# USB_PD_CONTROLLER.net
KiCad netlist of a schematic drawn in Altium Designer
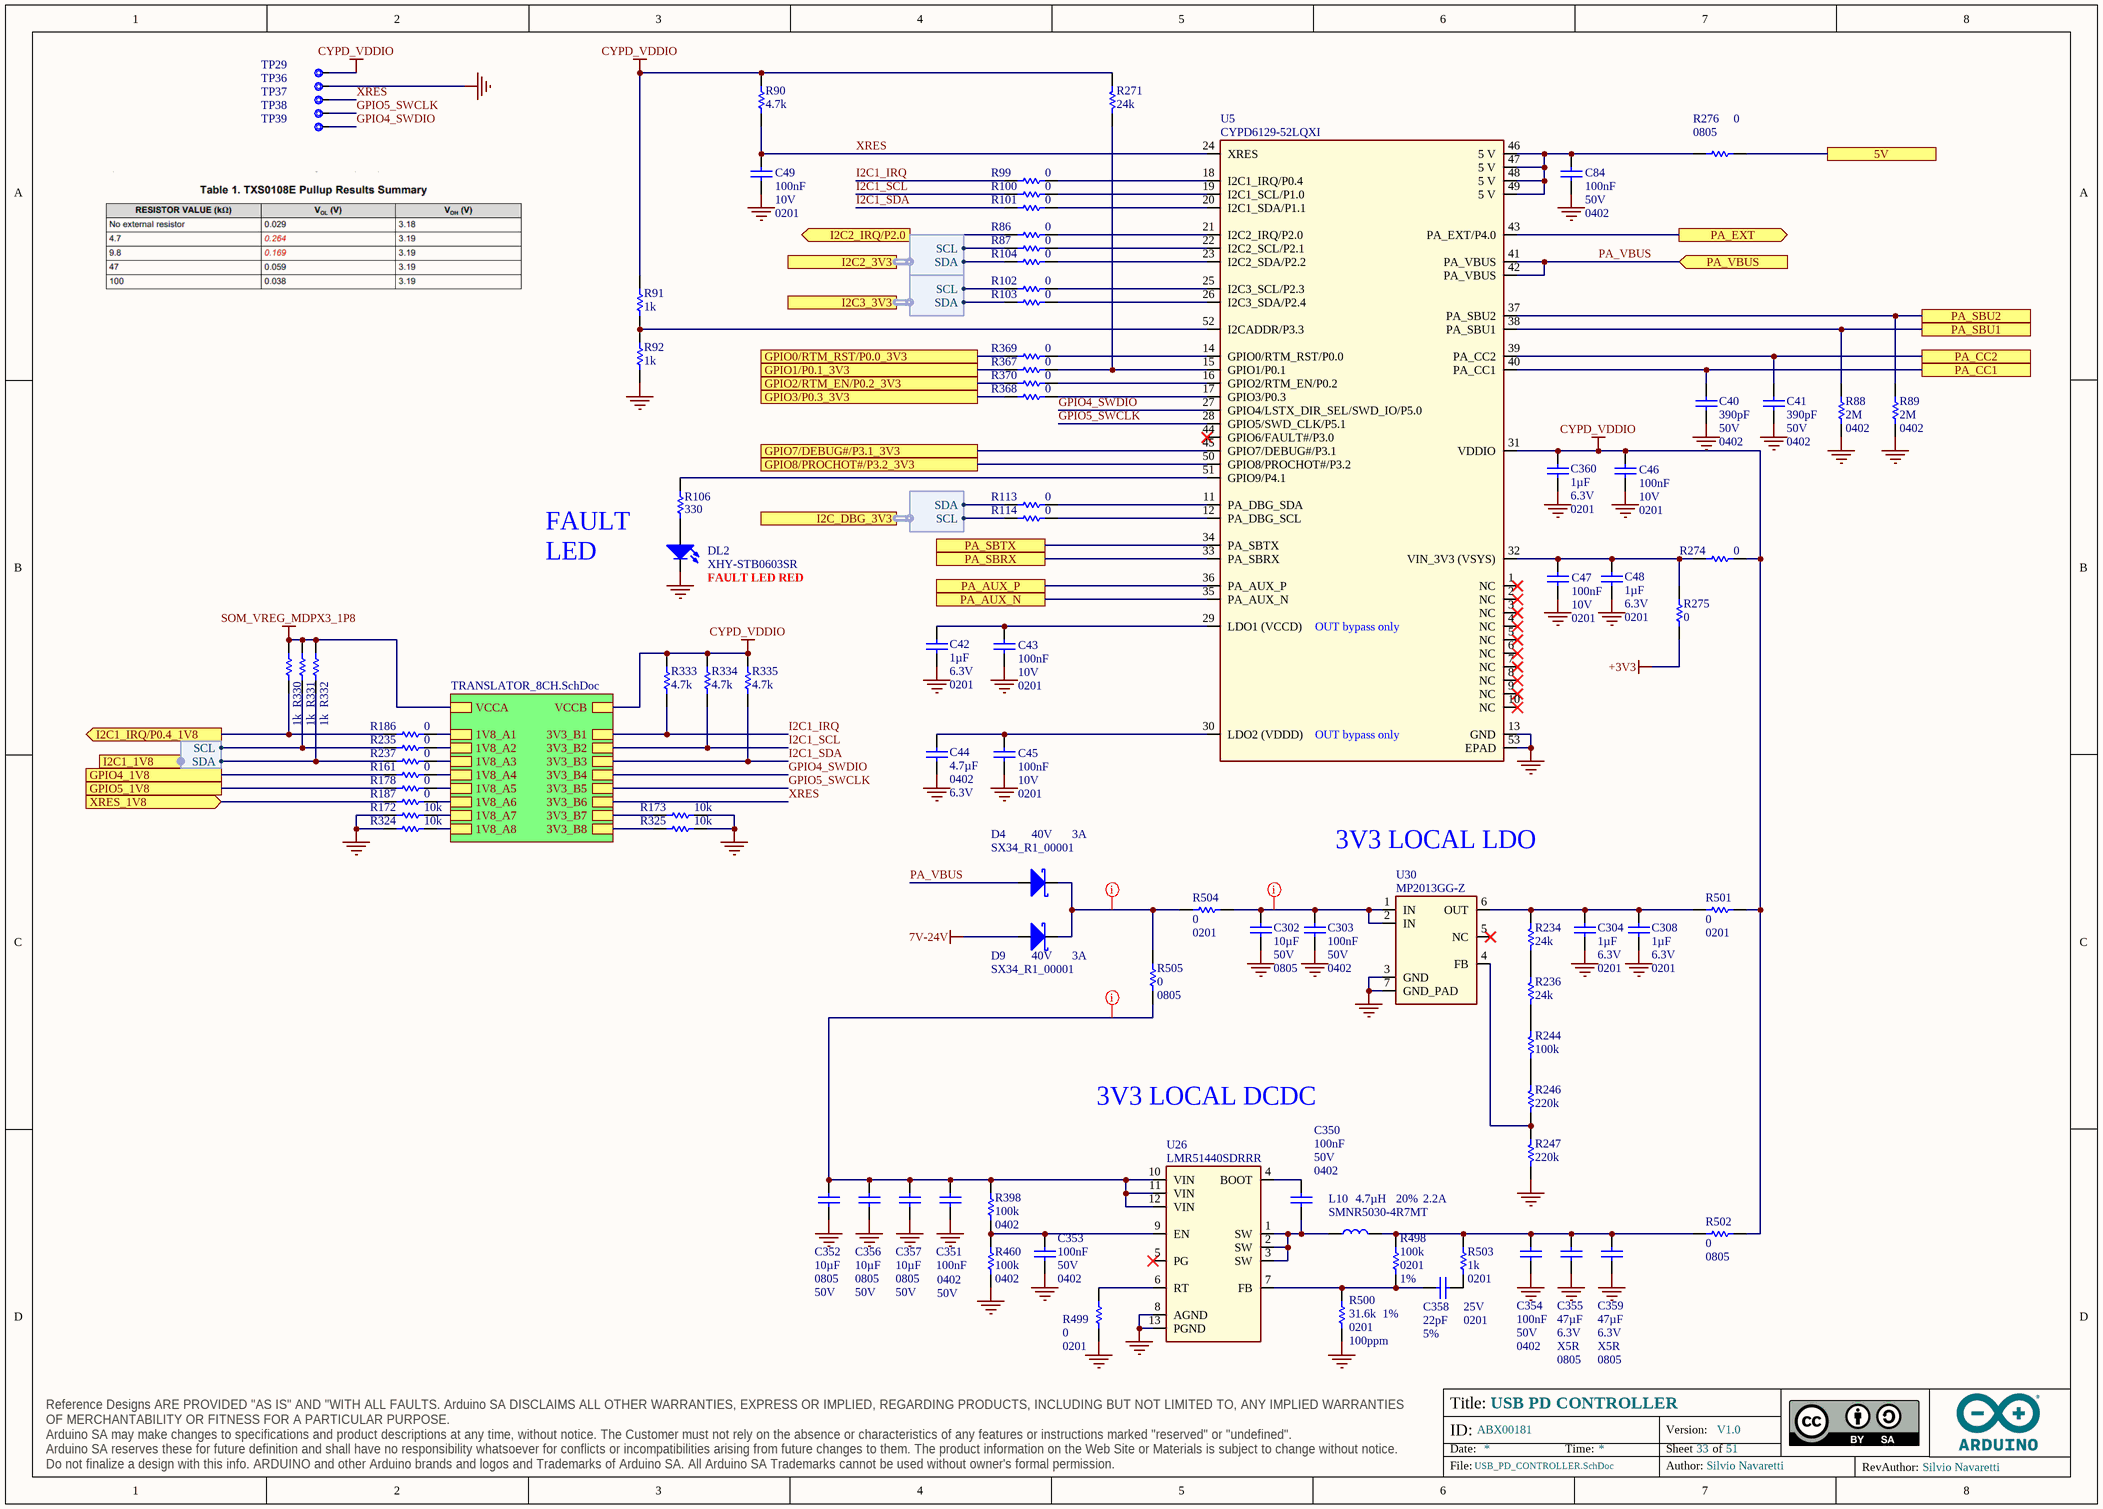
[diagram p0: USB_PD_CONTROLLER.SchDoc]

(export (version "E")
  (design (tool "Eeschema 10.0.6"))
  (components
    (comp (ref "C40")
      (value "390pF")
      (footprint "CAP-0402")
      (description "CAP CHIP 0402 390pF 10% 50V X7R")
      (fields
        (field (name "MANUFACTURER") "Murata")
        (field (name "PART NUMBER") "CL05B391KB5NNNC")
        (field (name "VOLTAGE") "50V")
        (field (name "CASE CODE (IMPERIAL)") "0402")
      )
      (libsource (lib "Clean") (part "CAP"))
    )
    (comp (ref "C41")
      (value "390pF")
      (footprint "CAP-0402")
      (description "CAP CHIP 0402 390pF 10% 50V X7R")
      (fields
        (field (name "MANUFACTURER") "Murata")
        (field (name "PART NUMBER") "CL05B391KB5NNNC")
        (field (name "VOLTAGE") "50V")
        (field (name "CASE CODE (IMPERIAL)") "0402")
      )
      (libsource (lib "Clean") (part "CAP"))
    )
    (comp (ref "C42")
      (value "1µF")
      (footprint "CAP-0201")
      (description "CAP CHIP 0201 1uF 20% 6.3V X5R")
      (fields
        (field (name "VOLTAGE") "6.3V")
        (field (name "TOLERANCE") "20%")
        (field (name "PART NUMBER") "GRM033R60J105MEA2D")
        (field (name "CASE CODE (IMPERIAL)") "0201")
      )
      (libsource (lib "Clean") (part "CAP"))
    )
    (comp (ref "C43")
      (value "100nF")
      (footprint "CAP-0201")
      (description "CAP CHIP 0201 100nF 10% 10V X5R")
      (fields
        (field (name "PART NUMBER") "CL03A104KP3NNNC")
        (field (name "MANUFACTURER") "Samsung Electro-Mechanics")
        (field (name "VOLTAGE") "10V")
        (field (name "CASE CODE (IMPERIAL)") "0201")
      )
      (libsource (lib "Clean") (part "CAP"))
    )
    (comp (ref "C44")
      (value "4.7µF")
      (footprint "CAP-0402")
      (description "CAP CHIP 0402 4.7uF 20% 6V3 X5R")
      (fields
        (field (name "MANUFACTURER") "Hottech")
        (field (name "PART NUMBER") "C1005A475M6R3NT")
        (field (name "CASE CODE (IMPERIAL)") "0402")
        (field (name "VOLTAGE") "6.3V")
      )
      (libsource (lib "Clean") (part "CAP"))
    )
    (comp (ref "C45")
      (value "100nF")
      (footprint "CAP-0201")
      (description "CAP CHIP 0201 100nF 10% 10V X5R")
      (fields
        (field (name "PART NUMBER") "CL03A104KP3NNNC")
        (field (name "MANUFACTURER") "Samsung Electro-Mechanics")
        (field (name "VOLTAGE") "10V")
        (field (name "CASE CODE (IMPERIAL)") "0201")
      )
      (libsource (lib "Clean") (part "CAP"))
    )
    (comp (ref "C46")
      (value "100nF")
      (footprint "CAP-0201")
      (description "CAP CHIP 0201 100nF 10% 10V X5R")
      (fields
        (field (name "PART NUMBER") "CL03A104KP3NNNC")
        (field (name "MANUFACTURER") "Samsung Electro-Mechanics")
        (field (name "VOLTAGE") "10V")
        (field (name "CASE CODE (IMPERIAL)") "0201")
      )
      (libsource (lib "Clean") (part "CAP"))
    )
    (comp (ref "C47")
      (value "100nF")
      (footprint "CAP-0201")
      (description "CAP CHIP 0201 100nF 10% 10V X5R")
      (fields
        (field (name "PART NUMBER") "CL03A104KP3NNNC")
        (field (name "MANUFACTURER") "Samsung Electro-Mechanics")
        (field (name "VOLTAGE") "10V")
        (field (name "CASE CODE (IMPERIAL)") "0201")
      )
      (libsource (lib "Clean") (part "CAP"))
    )
    (comp (ref "C48")
      (value "1µF")
      (footprint "CAP-0201")
      (description "CAP CHIP 0201 1uF 20% 6.3V X5R")
      (fields
        (field (name "VOLTAGE") "6.3V")
        (field (name "TOLERANCE") "20%")
        (field (name "PART NUMBER") "GRM033R60J105MEA2D")
        (field (name "CASE CODE (IMPERIAL)") "0201")
      )
      (libsource (lib "Clean") (part "CAP"))
    )
    (comp (ref "C49")
      (value "100nF")
      (footprint "CAP-0201")
      (description "CAP CHIP 0201 100nF 10% 10V X5R")
      (fields
        (field (name "PART NUMBER") "CL03A104KP3NNNC")
        (field (name "MANUFACTURER") "Samsung Electro-Mechanics")
        (field (name "VOLTAGE") "10V")
        (field (name "CASE CODE (IMPERIAL)") "0201")
      )
      (libsource (lib "Clean") (part "CAP"))
    )
    (comp (ref "C84")
      (value "100nF")
      (footprint "CAP-0402")
      (description "CAP CHIP 0402 100nF 10% 50V X5R")
      (fields
        (field (name "PART NUMBER") "GRM155R61H104KE19D")
        (field (name "MANUFACTURER") "Murata")
        (field (name "VOLTAGE") "50V")
        (field (name "CASE CODE (IMPERIAL)") "0402")
      )
      (libsource (lib "Clean") (part "CAP"))
    )
    (comp (ref "C302")
      (value "10µF")
      (footprint "CAP-0805")
      (description "CAP CHIP 0805 10uF 20% 50V X5R")
      (fields
        (field (name "VOLTAGE") "50V")
        (field (name "PART NUMBER") "GRM21BR61H106ME43L")
        (field (name "CASE CODE (IMPERIAL)") "0805")
        (field (name "MANUFACTURER") "Murata Electronics")
      )
      (libsource (lib "Clean") (part "CAP"))
    )
    (comp (ref "C303")
      (value "100nF")
      (footprint "CAP-0402")
      (description "CAP CHIP 0402 100nF 10% 50V X5R")
      (fields
        (field (name "MANUFACTURER") "Murata")
        (field (name "PART NUMBER") "GRM155R61H104KE19D")
        (field (name "VOLTAGE") "50V")
        (field (name "CASE CODE (IMPERIAL)") "0402")
      )
      (libsource (lib "Clean") (part "CAP"))
    )
    (comp (ref "C304")
      (value "1µF")
      (footprint "CAP-0201")
      (description "CAP CHIP 0201 1uF 20% 6.3V X5R")
      (fields
        (field (name "VOLTAGE") "6.3V")
        (field (name "TOLERANCE") "20%")
        (field (name "PART NUMBER") "GRM033R60J105MEA2D")
        (field (name "CASE CODE (IMPERIAL)") "0201")
      )
      (libsource (lib "Clean") (part "CAP"))
    )
    (comp (ref "C308")
      (value "1µF")
      (footprint "CAP-0201")
      (description "CAP CHIP 0201 1uF 20% 6.3V X5R")
      (fields
        (field (name "VOLTAGE") "6.3V")
        (field (name "TOLERANCE") "20%")
        (field (name "PART NUMBER") "GRM033R60J105MEA2D")
        (field (name "CASE CODE (IMPERIAL)") "0201")
      )
      (libsource (lib "Clean") (part "CAP"))
    )
    (comp (ref "C350")
      (value "100nF")
      (footprint "CAP-0402")
      (description "CAP CHIP 0402 100nF 10% 50V X5R")
      (fields
        (field (name "MANUFACTURER") "Murata")
        (field (name "PART NUMBER") "GRM155R61H104KE19D")
        (field (name "VOLTAGE") "50V")
        (field (name "CASE CODE (IMPERIAL)") "0402")
      )
      (libsource (lib "Clean") (part "CAP"))
    )
    (comp (ref "C351")
      (value "100nF")
      (footprint "CAP-0402")
      (description "CAP CHIP 0402 100nF 10% 50V X5R")
      (fields
        (field (name "MANUFACTURER") "Murata")
        (field (name "PART NUMBER") "GRM155R61H104KE19D")
        (field (name "VOLTAGE") "50V")
        (field (name "CASE CODE (IMPERIAL)") "0402")
      )
      (libsource (lib "Clean") (part "CAP"))
    )
    (comp (ref "C352")
      (value "10µF")
      (footprint "CAP-0805")
      (description "CAP CHIP 0805 10uF 20% 50V X5R")
      (fields
        (field (name "CASE CODE (IMPERIAL)") "0805")
        (field (name "TOLERANCE") "20%")
        (field (name "PART NUMBER") "GRM21BR61H106ME43L")
        (field (name "VOLTAGE") "50V")
      )
      (libsource (lib "Clean") (part "CAP"))
    )
    (comp (ref "C353")
      (value "100nF")
      (footprint "CAP-0402")
      (description "CAP CHIP 0402 100nF 10% 50V X5R")
      (fields
        (field (name "MANUFACTURER") "Murata")
        (field (name "PART NUMBER") "GRM155R61H104KE19D")
        (field (name "VOLTAGE") "50V")
        (field (name "CASE CODE (IMPERIAL)") "0402")
      )
      (libsource (lib "Clean") (part "CAP"))
    )
    (comp (ref "C354")
      (value "100nF")
      (footprint "CAP-0402")
      (description "CAP CHIP 0402 100nF 10% 50V X5R")
      (fields
        (field (name "MANUFACTURER") "Murata")
        (field (name "PART NUMBER") "GRM155R61H104KE19D")
        (field (name "VOLTAGE") "50V")
        (field (name "CASE CODE (IMPERIAL)") "0402")
      )
      (libsource (lib "Clean") (part "CAP"))
    )
    (comp (ref "C355")
      (value "47µF")
      (footprint "CAP-0805")
      (description "CAP CHIP 0805 47uF 20% 6.3V X5R")
      (fields
        (field (name "VOLTAGE") "6.3V")
        (field (name "DIELECTRIC") "X5R")
        (field (name "TOLERANCE") "20%")
        (field (name "CASE CODE (IMPERIAL)") "0805")
        (field (name "MANUFACTURER") "KEMET")
      )
      (libsource (lib "Clean") (part "CAP"))
    )
    (comp (ref "C356")
      (value "10µF")
      (footprint "CAP-0805")
      (description "CAP CHIP 0805 10uF 20% 50V X5R")
      (fields
        (field (name "CASE CODE (IMPERIAL)") "0805")
        (field (name "TOLERANCE") "20%")
        (field (name "PART NUMBER") "GRM21BR61H106ME43L")
        (field (name "VOLTAGE") "50V")
      )
      (libsource (lib "Clean") (part "CAP"))
    )
    (comp (ref "C357")
      (value "10µF")
      (footprint "CAP-0805")
      (description "CAP CHIP 0805 10uF 20% 50V X5R")
      (fields
        (field (name "CASE CODE (IMPERIAL)") "0805")
        (field (name "TOLERANCE") "20%")
        (field (name "PART NUMBER") "GRM21BR61H106ME43L")
        (field (name "VOLTAGE") "50V")
      )
      (libsource (lib "Clean") (part "CAP"))
    )
    (comp (ref "C358")
      (value "22pF")
      (footprint "CAP-0201")
      (description "CAP CHIP 0201 22pF 5% 25V C0G")
      (fields
        (field (name "TOLERANCE") "5%")
        (field (name "PART NUMBER") "CC0201JPNPO8BN220")
        (field (name "CASE CODE (IMPERIAL)") "0201")
        (field (name "MANUFACTURER") "Yageo")
        (field (name "VOLTAGE") "25V")
      )
      (libsource (lib "Clean") (part "CAP"))
    )
    (comp (ref "C359")
      (value "47µF")
      (footprint "CAP-0805")
      (description "CAP CHIP 0805 47uF 20% 6.3V X5R")
      (fields
        (field (name "VOLTAGE") "6.3V")
        (field (name "DIELECTRIC") "X5R")
        (field (name "TOLERANCE") "20%")
        (field (name "CASE CODE (IMPERIAL)") "0805")
        (field (name "MANUFACTURER") "KEMET")
      )
      (libsource (lib "Clean") (part "CAP"))
    )
    (comp (ref "C360")
      (value "1µF")
      (footprint "CAP-0201")
      (description "CAP CHIP 0201 1uF 20% 6.3V X5R")
      (fields
        (field (name "VOLTAGE") "6.3V")
        (field (name "TOLERANCE") "20%")
        (field (name "PART NUMBER") "GRM033R60J105MEA2D")
        (field (name "CASE CODE (IMPERIAL)") "0201")
      )
      (libsource (lib "Clean") (part "CAP"))
    )
    (comp (ref "D4")
      (value "SX34_R1_00001")
      (footprint "SMA DO214AC")
      (description "DIODE SCHOTTKY SMD 3A 40V SMA DO214AC")
      (fields
        (field (name "PART NUMBER") "SX34-AU_R1_000A1")
        (field (name "MANUFACTURER") "Panjit")
        (field (name "MAX REVERSE VOLTAGE (DC)") "40V")
        (field (name "FORWARD CURRENT") "3A")
      )
      (libsource (lib "Clean") (part "Diode Schottky"))
    )
    (comp (ref "D9")
      (value "SX34_R1_00001")
      (footprint "SMA DO214AC")
      (description "DIODE SCHOTTKY SMD 3A 40V SMA DO214AC")
      (fields
        (field (name "PART NUMBER") "SX34-AU_R1_000A1")
        (field (name "MANUFACTURER") "Panjit")
        (field (name "MAX REVERSE VOLTAGE (DC)") "40V")
        (field (name "FORWARD CURRENT") "3A")
      )
      (libsource (lib "Clean") (part "Diode Schottky"))
    )
    (comp (ref "DL2")
      (value "XHY-STB0603SR")
      (footprint "LEDC1608X80N-AK")
      (description "LED SMD 0603 RED 625nm, water clear, 42 to 88 mcd, 120 degrees, 1.6x0.8x0.6mm")
      (fields (field (name "MANUFACTURER") "Shenzen Corehy Technology"))
      (libsource (lib "Clean") (part "LED"))
    )
    (comp (ref "L10")
      (value "SMNR5030-4R7MT")
      (footprint "Inductor 5030")
      (description "IND SMD 4.7uH 20%, DCR max 65mR, I sat 3A, I RMS 2.2A, package 5x5mm height 3mm")
      (fields
        (field (name "MANUFACTURER") "Shun Xiang Nuo")
        (field (name "TOLERANCE") "20%")
        (field (name "IRMS") "2.2A")
        (field (name "INDUCTANCE") "4.7µH")
      )
      (libsource (lib "Clean") (part "Inductor"))
    )
    (comp (ref "R86")
      (value "0")
      (footprint "RES-0201")
      (description "RES CHIP 0201 0R")
      (fields (field (name "MANUFACTURER") "Vishay") (field (name "PART NUMBER") "CRCW02010000Z0ED"))
      (libsource (lib "Clean") (part "RES"))
    )
    (comp (ref "R87")
      (value "0")
      (footprint "RES-0201")
      (description "RES CHIP 0201 0R")
      (fields (field (name "MANUFACTURER") "Vishay") (field (name "PART NUMBER") "CRCW02010000Z0ED"))
      (libsource (lib "Clean") (part "RES"))
    )
    (comp (ref "R88")
      (value "2M")
      (footprint "RES-0402")
      (description "RES CHIP 0402 2M 1% 1/16W")
      (fields
        (field (name "PART NUMBER") "RC0402FR-072ML")
        (field (name "CASE CODE (IMPERIAL)") "0402")
        (field (name "MANUFACTURER") "YAGEO")
      )
      (libsource (lib "Clean") (part "RES"))
    )
    (comp (ref "R89")
      (value "2M")
      (footprint "RES-0402")
      (description "RES CHIP 0402 2M 1% 1/16W")
      (fields
        (field (name "PART NUMBER") "RC0402FR-072ML")
        (field (name "CASE CODE (IMPERIAL)") "0402")
        (field (name "MANUFACTURER") "YAGEO")
      )
      (libsource (lib "Clean") (part "RES"))
    )
    (comp (ref "R90")
      (value "4.7k")
      (footprint "RES-0201")
      (description "RES CHIP 0201 4k7 1% 1/20W")
      (fields (field (name "POWER") "50mW") (field (name "TOLERANCE") "1%"))
      (libsource (lib "Clean") (part "RES"))
    )
    (comp (ref "R91")
      (value "1k")
      (footprint "RES-0201")
      (description "RES CHIP 0201 1k 1% 1/20W")
      (fields (field (name "PART NUMBER") "RC0201FR-071KL") (field (name "TOLERANCE") "1%"))
      (libsource (lib "Clean") (part "RES"))
    )
    (comp (ref "R92")
      (value "1k")
      (footprint "RES-0201")
      (description "RES CHIP 0201 1k 1% 1/20W")
      (fields (field (name "PART NUMBER") "RC0201FR-071KL") (field (name "TOLERANCE") "1%"))
      (libsource (lib "Clean") (part "RES"))
    )
    (comp (ref "R99")
      (value "0")
      (footprint "RES-0201")
      (description "RES CHIP 0201 0R")
      (fields (field (name "MANUFACTURER") "Vishay") (field (name "PART NUMBER") "CRCW02010000Z0ED"))
      (libsource (lib "Clean") (part "RES"))
    )
    (comp (ref "R100")
      (value "0")
      (footprint "RES-0201")
      (description "RES CHIP 0201 0R")
      (fields (field (name "MANUFACTURER") "Vishay") (field (name "PART NUMBER") "CRCW02010000Z0ED"))
      (libsource (lib "Clean") (part "RES"))
    )
    (comp (ref "R101")
      (value "0")
      (footprint "RES-0201")
      (description "RES CHIP 0201 0R")
      (fields (field (name "MANUFACTURER") "Vishay") (field (name "PART NUMBER") "CRCW02010000Z0ED"))
      (libsource (lib "Clean") (part "RES"))
    )
    (comp (ref "R102")
      (value "0")
      (footprint "RES-0201")
      (description "RES CHIP 0201 0R")
      (fields (field (name "MANUFACTURER") "Vishay") (field (name "PART NUMBER") "CRCW02010000Z0ED"))
      (libsource (lib "Clean") (part "RES"))
    )
    (comp (ref "R103")
      (value "0")
      (footprint "RES-0201")
      (description "RES CHIP 0201 0R")
      (fields (field (name "MANUFACTURER") "Vishay") (field (name "PART NUMBER") "CRCW02010000Z0ED"))
      (libsource (lib "Clean") (part "RES"))
    )
    (comp (ref "R104")
      (value "0")
      (footprint "RES-0201")
      (description "RES CHIP 0201 0R")
      (fields (field (name "MANUFACTURER") "Vishay") (field (name "PART NUMBER") "CRCW02010000Z0ED"))
      (libsource (lib "Clean") (part "RES"))
    )
    (comp (ref "R106")
      (value "330")
      (footprint "RES-0201")
      (description "RES CHIP 0201 330R 1% 1/20W")
      (fields (field (name "MANUFACTURER") "Yageo") (field (name "POWER") "50mW"))
      (libsource (lib "Clean") (part "RES"))
    )
    (comp (ref "R113")
      (value "0")
      (footprint "RES-0201")
      (description "RES CHIP 0201 0R")
      (fields (field (name "MANUFACTURER") "Vishay") (field (name "PART NUMBER") "CRCW02010000Z0ED"))
      (libsource (lib "Clean") (part "RES"))
    )
    (comp (ref "R114")
      (value "0")
      (footprint "RES-0201")
      (description "RES CHIP 0201 0R")
      (fields (field (name "MANUFACTURER") "Vishay") (field (name "PART NUMBER") "CRCW02010000Z0ED"))
      (libsource (lib "Clean") (part "RES"))
    )
    (comp (ref "R161")
      (value "0")
      (footprint "RES-0201")
      (description "RES CHIP 0201 0R")
      (fields (field (name "MANUFACTURER") "Vishay") (field (name "PART NUMBER") "CRCW02010000Z0ED"))
      (libsource (lib "Clean") (part "RES"))
    )
    (comp (ref "R172")
      (value "10k")
      (footprint "RES-0201")
      (description "RES CHIP 0201 10k 1% 1/20W")
      (fields (field (name "POWER") "50mW") (field (name "TOLERANCE") "1%"))
      (libsource (lib "Clean") (part "RES"))
    )
    (comp (ref "R173")
      (value "10k")
      (footprint "RES-0201")
      (description "RES CHIP 0201 10k 1% 1/20W")
      (fields (field (name "POWER") "50mW") (field (name "TOLERANCE") "1%"))
      (libsource (lib "Clean") (part "RES"))
    )
    (comp (ref "R178")
      (value "0")
      (footprint "RES-0201")
      (description "RES CHIP 0201 0R")
      (fields (field (name "MANUFACTURER") "Vishay") (field (name "PART NUMBER") "CRCW02010000Z0ED"))
      (libsource (lib "Clean") (part "RES"))
    )
    (comp (ref "R186")
      (value "0")
      (footprint "RES-0201")
      (description "RES CHIP 0201 0R")
      (fields (field (name "MANUFACTURER") "Vishay") (field (name "PART NUMBER") "CRCW02010000Z0ED"))
      (libsource (lib "Clean") (part "RES"))
    )
    (comp (ref "R187")
      (value "0")
      (footprint "RES-0201")
      (description "RES CHIP 0201 0R")
      (fields (field (name "MANUFACTURER") "Vishay") (field (name "PART NUMBER") "CRCW02010000Z0ED"))
      (libsource (lib "Clean") (part "RES"))
    )
    (comp (ref "R234")
      (value "24k")
      (footprint "RES-0201")
      (description "RES CHIP 0201 24k 1% 1/20W")
      (fields (field (name "POWER") "50mW") (field (name "PART NUMBER") "RC0201FR-0724KL"))
      (libsource (lib "Clean") (part "RES"))
    )
    (comp (ref "R235")
      (value "0")
      (footprint "RES-0201")
      (description "RES CHIP 0201 0R")
      (fields (field (name "MANUFACTURER") "Vishay") (field (name "PART NUMBER") "CRCW02010000Z0ED"))
      (libsource (lib "Clean") (part "RES"))
    )
    (comp (ref "R236")
      (value "24k")
      (footprint "RES-0201")
      (description "RES CHIP 0201 24k 1% 1/20W")
      (fields (field (name "POWER") "50mW") (field (name "PART NUMBER") "RC0201FR-0724KL"))
      (libsource (lib "Clean") (part "RES"))
    )
    (comp (ref "R237")
      (value "0")
      (footprint "RES-0201")
      (description "RES CHIP 0201 0R")
      (fields (field (name "MANUFACTURER") "Vishay") (field (name "PART NUMBER") "CRCW02010000Z0ED"))
      (libsource (lib "Clean") (part "RES"))
    )
    (comp (ref "R244")
      (value "100k")
      (footprint "RES-0201")
      (description "RES CHIP 0201 100k 1% 1/20W")
      (fields (field (name "POWER") "50mW") (field (name "TOLERANCE") "1%"))
      (libsource (lib "Clean") (part "RES"))
    )
    (comp (ref "R246")
      (value "220k")
      (footprint "RES-0201")
      (description "RES CHIP 0201 220k 1% 1/20W")
      (fields (field (name "PART NUMBER") "AC0201FR-07220KL") (field (name "TOLERANCE") "1%"))
      (libsource (lib "Clean") (part "RES"))
    )
    (comp (ref "R247")
      (value "220k")
      (footprint "RES-0201")
      (description "RES CHIP 0201 220k 1% 1/20W")
      (fields (field (name "PART NUMBER") "AC0201FR-07220KL") (field (name "TOLERANCE") "1%"))
      (libsource (lib "Clean") (part "RES"))
    )
    (comp (ref "R271")
      (value "24k")
      (footprint "RES-0201")
      (description "RES CHIP 0201 24k 1% 1/20W")
      (fields (field (name "POWER") "50mW") (field (name "PART NUMBER") "RC0201FR-0724KL"))
      (libsource (lib "Clean") (part "RES"))
    )
    (comp (ref "R274")
      (value "0")
      (footprint "RES-0201")
      (description "RES CHIP 0201 0R")
      (fields (field (name "MANUFACTURER") "Vishay") (field (name "PART NUMBER") "CRCW02010000Z0ED"))
      (libsource (lib "Clean") (part "RES"))
    )
    (comp (ref "R275")
      (value "0")
      (footprint "RES-0201")
      (description "RES CHIP 0201 0R")
      (fields (field (name "MANUFACTURER") "Vishay") (field (name "PART NUMBER") "CRCW02010000Z0ED"))
      (libsource (lib "Clean") (part "RES"))
    )
    (comp (ref "R276")
      (value "0")
      (footprint "RES-0805")
      (description "RES CHIP 0805 0R")
      (fields
        (field (name "MANUFACTURER") "Vishay")
        (field (name "CASE CODE (IMPERIAL)") "0805")
        (field (name "PART NUMBER") "CRCW08050000Z0EB")
      )
      (libsource (lib "Clean") (part "RES"))
    )
    (comp (ref "R324")
      (value "10k")
      (footprint "RES-0201")
      (description "RES CHIP 0201 10k 1% 1/20W")
      (fields (field (name "POWER") "50mW") (field (name "TOLERANCE") "1%"))
      (libsource (lib "Clean") (part "RES"))
    )
    (comp (ref "R325")
      (value "10k")
      (footprint "RES-0201")
      (description "RES CHIP 0201 10k 1% 1/20W")
      (fields (field (name "POWER") "50mW") (field (name "TOLERANCE") "1%"))
      (libsource (lib "Clean") (part "RES"))
    )
    (comp (ref "R330")
      (value "1k")
      (footprint "RES-0201")
      (description "RES CHIP 0201 1k 1% 1/20W")
      (fields (field (name "POWER") "50mW") (field (name "TOLERANCE") "1%"))
      (libsource (lib "Clean") (part "RES"))
    )
    (comp (ref "R331")
      (value "1k")
      (footprint "RES-0201")
      (description "RES CHIP 0201 1k 1% 1/20W")
      (fields (field (name "POWER") "50mW") (field (name "TOLERANCE") "1%"))
      (libsource (lib "Clean") (part "RES"))
    )
    (comp (ref "R332")
      (value "1k")
      (footprint "RES-0201")
      (description "RES CHIP 0201 1k 1% 1/20W")
      (fields (field (name "POWER") "50mW") (field (name "TOLERANCE") "1%"))
      (libsource (lib "Clean") (part "RES"))
    )
    (comp (ref "R333")
      (value "4.7k")
      (footprint "RES-0201")
      (description "RES CHIP 0201 4k7 1% 1/20W")
      (fields (field (name "POWER") "50mW") (field (name "TOLERANCE") "1%"))
      (libsource (lib "Clean") (part "RES"))
    )
    (comp (ref "R334")
      (value "4.7k")
      (footprint "RES-0201")
      (description "RES CHIP 0201 4k7 1% 1/20W")
      (fields (field (name "POWER") "50mW") (field (name "TOLERANCE") "1%"))
      (libsource (lib "Clean") (part "RES"))
    )
    (comp (ref "R335")
      (value "4.7k")
      (footprint "RES-0201")
      (description "RES CHIP 0201 4k7 1% 1/20W")
      (fields (field (name "POWER") "50mW") (field (name "TOLERANCE") "1%"))
      (libsource (lib "Clean") (part "RES"))
    )
    (comp (ref "R367")
      (value "0")
      (footprint "RES-0201")
      (description "RES CHIP 0201 0R")
      (fields (field (name "MANUFACTURER") "Vishay") (field (name "PART NUMBER") "CRCW02010000Z0ED"))
      (libsource (lib "Clean") (part "RES"))
    )
    (comp (ref "R368")
      (value "0")
      (footprint "RES-0201")
      (description "RES CHIP 0201 0R")
      (fields (field (name "MANUFACTURER") "Vishay") (field (name "PART NUMBER") "CRCW02010000Z0ED"))
      (libsource (lib "Clean") (part "RES"))
    )
    (comp (ref "R369")
      (value "0")
      (footprint "RES-0201")
      (description "RES CHIP 0201 0R")
      (fields (field (name "MANUFACTURER") "Vishay") (field (name "PART NUMBER") "CRCW02010000Z0ED"))
      (libsource (lib "Clean") (part "RES"))
    )
    (comp (ref "R370")
      (value "0")
      (footprint "RES-0201")
      (description "RES CHIP 0201 0R")
      (fields (field (name "MANUFACTURER") "Vishay") (field (name "PART NUMBER") "CRCW02010000Z0ED"))
      (libsource (lib "Clean") (part "RES"))
    )
    (comp (ref "R398")
      (value "100k")
      (footprint "RES-0402")
      (description "RES CHIP 0402 100k 1% 1/16W")
      (fields
        (field (name "MANUFACTURER") "Vishay")
        (field (name "PART NUMBER") "CRCW0402100KFKEDC")
        (field (name "CASE CODE (IMPERIAL)") "0402")
      )
      (libsource (lib "Clean") (part "RES"))
    )
    (comp (ref "R460")
      (value "100k")
      (footprint "RES-0402")
      (description "RES CHIP 0402 100k 1% 1/16W")
      (fields
        (field (name "MANUFACTURER") "Vishay")
        (field (name "PART NUMBER") "CRCW0402100KFKEDC")
        (field (name "CASE CODE (IMPERIAL)") "0402")
      )
      (libsource (lib "Clean") (part "RES"))
    )
    (comp (ref "R498")
      (value "100k")
      (footprint "RES-0201")
      (description "RES CHIP 0201 100k 1% 1/20W")
      (fields
        (field (name "MANUFACTURER") "Yageo")
        (field (name "PART NUMBER") "RC0201FR-07100KL")
        (field (name "TOLERANCE") "1%")
        (field (name "CASE CODE (IMPERIAL)") "0201")
      )
      (libsource (lib "Clean") (part "RES"))
    )
    (comp (ref "R499")
      (value "0")
      (footprint "RES-0201")
      (description "RES CHIP 0201 0R")
      (fields
        (field (name "MANUFACTURER") "Vishay")
        (field (name "CASE CODE (IMPERIAL)") "0201")
        (field (name "PART NUMBER") "CRCW02010000Z0ED")
      )
      (libsource (lib "Clean") (part "RES"))
    )
    (comp (ref "R500")
      (value "31.6k")
      (footprint "RES-0201")
      (description "RES CHIP 0201 31k6 1% 1/20W 100ppm")
      (fields
        (field (name "POWER") "50mW")
        (field (name "PART NUMBER") "CRCW020131K6FKED")
        (field (name "CASE CODE (IMPERIAL)") "0201")
        (field (name "TOLERANCE") "1%")
        (field (name "TEMPERATURE COEFFICIENT") "100ppm")
      )
      (libsource (lib "Clean") (part "RES"))
    )
    (comp (ref "R501")
      (value "0")
      (footprint "RES-0201")
      (description "RES CHIP 0201 0R")
      (fields
        (field (name "MANUFACTURER") "Vishay")
        (field (name "CASE CODE (IMPERIAL)") "0201")
        (field (name "PART NUMBER") "CRCW02010000Z0ED")
      )
      (libsource (lib "Clean") (part "RES"))
    )
    (comp (ref "R502")
      (value "0")
      (footprint "RES-0805")
      (description "RES CHIP 0805 0R")
      (fields
        (field (name "MANUFACTURER") "Vishay")
        (field (name "CASE CODE (IMPERIAL)") "0805")
        (field (name "PART NUMBER") "CRCW08050000Z0EB")
      )
      (libsource (lib "Clean") (part "RES"))
    )
    (comp (ref "R503")
      (value "1k")
      (footprint "RES-0201")
      (description "RES CHIP 0201 1k 1% 1/20W")
      (fields
        (field (name "PART NUMBER") "RC0201FR-071KL")
        (field (name "TOLERANCE") "1%")
        (field (name "CASE CODE (IMPERIAL)") "0201")
      )
      (libsource (lib "Clean") (part "RES"))
    )
    (comp (ref "R504")
      (value "0")
      (footprint "RES-0201")
      (description "RES CHIP 0201 0R")
      (fields
        (field (name "MANUFACTURER") "Vishay")
        (field (name "CASE CODE (IMPERIAL)") "0201")
        (field (name "PART NUMBER") "CRCW02010000Z0ED")
      )
      (libsource (lib "Clean") (part "RES"))
    )
    (comp (ref "R505")
      (value "0")
      (footprint "RES-0805")
      (description "RES CHIP 0805 0R")
      (fields
        (field (name "MANUFACTURER") "Vishay")
        (field (name "CASE CODE (IMPERIAL)") "0805")
        (field (name "PART NUMBER") "CRCW08050000Z0EB")
      )
      (libsource (lib "Clean") (part "RES"))
    )
    (comp (ref "TP29")
      (value "Test point 1.00mm")
      (footprint "TP-1.00MM")
      (fields (field (name "PART NUMBER") "This is not a component"))
      (libsource (lib "Clean") (part "TESTPOINT"))
    )
    (comp (ref "TP36")
      (value "Test point 1.00mm")
      (footprint "TP-1.00MM")
      (fields (field (name "PART NUMBER") "This is not a component"))
      (libsource (lib "Clean") (part "TESTPOINT"))
    )
    (comp (ref "TP37")
      (value "Test point 1.00mm")
      (footprint "TP-1.00MM")
      (fields (field (name "PART NUMBER") "This is not a component"))
      (libsource (lib "Clean") (part "TESTPOINT"))
    )
    (comp (ref "TP38")
      (value "Test point 1.00mm")
      (footprint "TP-1.00MM")
      (fields (field (name "PART NUMBER") "This is not a component"))
      (libsource (lib "Clean") (part "TESTPOINT"))
    )
    (comp (ref "TP39")
      (value "Test point 1.00mm")
      (footprint "TP-1.00MM")
      (fields (field (name "PART NUMBER") "This is not a component"))
      (libsource (lib "Clean") (part "TESTPOINT"))
    )
    (comp (ref "U5")
      (value "CYPD6129-52LQXI")
      (footprint "QFN52 pitch 0.4mm, 5x8mm")
      (description "IC Controller power delivery USB-C, QFN52 5x8mm")
      (fields (field (name "MANUFACTURER") "Infineon"))
      (libsource (lib "Clean") (part "CYPD6129-52LQXI-Symbol-1"))
    )
    (comp (ref "U26")
      (value "LMR51440SDRRR")
      (footprint "WSON8 TI DDR 3x3mm 12 pins pitch 0.5mm")
      (description "IC BUCK Vin 4-36V, Iout 4A, max duty 97%, fsw 1.1MHz, WSON8 3x3mm")
      (fields (field (name "MANUFACTURER") "Texas Instruments"))
      (libsource (lib "Clean") (part "LMR51440SDRRR-Symbol-1"))
    )
    (comp (ref "U30")
      (value "MP2013GG-Z")
      (footprint "MPS QNF6 2x2mm 6pin pitch 0.65mm thermal pad")
      (description "IC LDO, Vin 2.5V-40V, Vout ADJ, Iout 0.15A, Iq typ 15uA, QFN6 2x2mm")
      (fields (field (name "MANUFACTURER") "MPS"))
      (libsource (lib "Clean") (part "MP2013GG-Z"))
    )
  )
  (nets
    (net (code "3") (name "+3V3") (class "Default")
      (node (ref "R275") (pin "1") (pinfunction "1_1") (pintype "passive"))
    )
    (net (code "4") (name "/1V8_A1") (class "Default")
      (node (ref "R186") (pin "2") (pinfunction "2_2") (pintype "passive"))
    )
    (net (code "5") (name "/1V8_A2") (class "Default")
      (node (ref "R235") (pin "2") (pinfunction "2_2") (pintype "passive"))
    )
    (net (code "6") (name "/1V8_A3") (class "Default")
      (node (ref "R237") (pin "2") (pinfunction "2_2") (pintype "passive"))
    )
    (net (code "7") (name "/1V8_A4") (class "Default")
      (node (ref "R161") (pin "2") (pinfunction "2_2") (pintype "passive"))
    )
    (net (code "8") (name "/1V8_A5") (class "Default")
      (node (ref "R178") (pin "2") (pinfunction "2_2") (pintype "passive"))
    )
    (net (code "9") (name "/1V8_A6") (class "Default")
      (node (ref "R187") (pin "2") (pinfunction "2_2") (pintype "passive"))
    )
    (net (code "10") (name "/1V8_A7") (class "Default")
      (node (ref "R172") (pin "2") (pinfunction "2_2") (pintype "passive"))
    )
    (net (code "11") (name "/1V8_A8") (class "Default")
      (node (ref "R324") (pin "2") (pinfunction "2_2") (pintype "passive"))
    )
    (net (code "12") (name "/3V3_B7") (class "Default")
      (node (ref "R173") (pin "1") (pinfunction "1_1") (pintype "passive"))
    )
    (net (code "13") (name "/3V3_B8") (class "Default")
      (node (ref "R325") (pin "1") (pinfunction "1_1") (pintype "passive"))
    )
    (net (code "14") (name "/5V") (class "Default")
      (node (ref "R276") (pin "2") (pinfunction "2_2") (pintype "passive"))
    )
    (net (code "15") (name "/GPIO0{slash}RTM_RST{slash}P0.0_3V3") (class "Default")
      (node (ref "R369") (pin "1") (pinfunction "1_1") (pintype "passive"))
    )
    (net (code "16") (name "/GPIO1{slash}P0.1_3V3") (class "Default")
      (node (ref "R367") (pin "1") (pinfunction "1_1") (pintype "passive"))
    )
    (net (code "17") (name "/GPIO2{slash}RTM_EN{slash}P0.2_3V3") (class "Default")
      (node (ref "R370") (pin "1") (pinfunction "1_1") (pintype "passive"))
    )
    (net (code "18") (name "/GPIO3{slash}P0.3_3V3") (class "Default")
      (node (ref "R368") (pin "1") (pinfunction "1_1") (pintype "passive"))
    )
    (net (code "19") (name "/GPIO4_1V8") (class "Default")
      (node (ref "R161") (pin "1") (pinfunction "1_1") (pintype "passive"))
    )
    (net (code "20") (name "/GPIO4_SWDIO") (class "Default")
      (node (ref "TP39") (pin "X") (pinfunction "X_X") (pintype "passive"))
      (node (ref "U5") (pin "27") (pinfunction "GPIO4/LSTX_DIR_SEL/SWD_IO/P5.0_27") (pintype "passive"))
    )
    (net (code "21") (name "/GPIO5_1V8") (class "Default")
      (node (ref "R178") (pin "1") (pinfunction "1_1") (pintype "passive"))
    )
    (net (code "22") (name "/GPIO5_SWCLK") (class "Default")
      (node (ref "TP38") (pin "X") (pinfunction "X_X") (pintype "passive"))
      (node (ref "U5") (pin "28") (pinfunction "GPIO5/SWD_CLK/P5.1_28") (pintype "passive"))
    )
    (net (code "23") (name "/GPIO7{slash}DEBUG#{slash}P3.1_3V3") (class "Default")
      (node (ref "U5") (pin "45") (pinfunction "GPIO7/DEBUG#/P3.1_45") (pintype "passive"))
    )
    (net (code "24") (name "/GPIO8{slash}PROCHOT#{slash}P3.2_3V3") (class "Default")
      (node (ref "U5") (pin "50") (pinfunction "GPIO8/PROCHOT#/P3.2_50") (pintype "passive"))
    )
    (net (code "25") (name "/I2C1_IRQ") (class "Default")
      (node (ref "R333") (pin "2") (pinfunction "2_2") (pintype "passive"))
      (node (ref "R99") (pin "1") (pinfunction "1_1") (pintype "passive"))
    )
    (net (code "26") (name "/I2C1_IRQ{slash}P0.4_1V8") (class "Default")
      (node (ref "R186") (pin "1") (pinfunction "1_1") (pintype "passive"))
      (node (ref "R330") (pin "2") (pinfunction "2_2") (pintype "passive"))
    )
    (net (code "27") (name "/I2C1_SCL") (class "Default")
      (node (ref "R100") (pin "1") (pinfunction "1_1") (pintype "passive"))
      (node (ref "R334") (pin "2") (pinfunction "2_2") (pintype "passive"))
    )
    (net (code "28") (name "/I2C1_SDA") (class "Default")
      (node (ref "R101") (pin "1") (pinfunction "1_1") (pintype "passive"))
      (node (ref "R335") (pin "2") (pinfunction "2_2") (pintype "passive"))
    )
    (net (code "30") (name "/I2C2_IRQ{slash}P2.0") (class "Default")
      (node (ref "R86") (pin "1") (pinfunction "1_1") (pintype "passive"))
    )
    (net (code "31") (name "/PA_AUX_N") (class "Default")
      (node (ref "U5") (pin "35") (pinfunction "PA_AUX_N_35") (pintype "passive"))
    )
    (net (code "32") (name "/PA_AUX_P") (class "Default")
      (node (ref "U5") (pin "36") (pinfunction "PA_AUX_P_36") (pintype "passive"))
    )
    (net (code "33") (name "/PA_CC1") (class "Default")
      (node (ref "C40") (pin "2") (pinfunction "2_2") (pintype "passive"))
      (node (ref "U5") (pin "40") (pinfunction "PA_CC1_40") (pintype "passive"))
    )
    (net (code "34") (name "/PA_CC2") (class "Default")
      (node (ref "C41") (pin "2") (pinfunction "2_2") (pintype "passive"))
      (node (ref "U5") (pin "39") (pinfunction "PA_CC2_39") (pintype "passive"))
    )
    (net (code "35") (name "/PA_EXT") (class "Default")
      (node (ref "U5") (pin "43") (pinfunction "PA_EXT/P4.0_43") (pintype "passive"))
    )
    (net (code "36") (name "/PA_SBRX") (class "Default")
      (node (ref "U5") (pin "33") (pinfunction "PA_SBRX_33") (pintype "passive"))
    )
    (net (code "37") (name "/PA_SBTX") (class "Default")
      (node (ref "U5") (pin "34") (pinfunction "PA_SBTX_34") (pintype "passive"))
    )
    (net (code "38") (name "/PA_SBU1") (class "Default")
      (node (ref "R88") (pin "2") (pinfunction "2_2") (pintype "passive"))
      (node (ref "U5") (pin "38") (pinfunction "PA_SBU1_38") (pintype "passive"))
    )
    (net (code "39") (name "/PA_SBU2") (class "Default")
      (node (ref "R89") (pin "2") (pinfunction "2_2") (pintype "passive"))
      (node (ref "U5") (pin "37") (pinfunction "PA_SBU2_37") (pintype "passive"))
    )
    (net (code "40") (name "/PA_VBUS") (class "Default")
      (node (ref "D4") (pin "A") (pinfunction "A_A") (pintype "passive"))
      (node (ref "U5") (pin "41") (pinfunction "PA_VBUS_41") (pintype "passive"))
      (node (ref "U5") (pin "42") (pinfunction "PA_VBUS_42") (pintype "passive"))
    )
    (net (code "41") (name "/XRES") (class "Default")
      (node (ref "C49") (pin "2") (pinfunction "2_2") (pintype "passive"))
      (node (ref "R90") (pin "2") (pinfunction "2_2") (pintype "passive"))
      (node (ref "TP37") (pin "X") (pinfunction "X_X") (pintype "passive"))
      (node (ref "U5") (pin "24") (pinfunction "XRES_24") (pintype "passive"))
    )
    (net (code "42") (name "/XRES_1V8") (class "Default")
      (node (ref "R187") (pin "1") (pinfunction "1_1") (pintype "passive"))
    )
    (net (code "44") (name "7V-24V") (class "Default")
      (node (ref "D9") (pin "A") (pinfunction "A_A") (pintype "passive"))
    )
    (net (code "45") (name "CYPD_VDDIO") (class "Default")
      (node (ref "C360") (pin "2") (pinfunction "2_2") (pintype "passive"))
      (node (ref "C46") (pin "2") (pinfunction "2_2") (pintype "passive"))
      (node (ref "R271") (pin "2") (pinfunction "2_2") (pintype "passive"))
      (node (ref "R274") (pin "2") (pinfunction "2_2") (pintype "passive"))
      (node (ref "R333") (pin "1") (pinfunction "1_1") (pintype "passive"))
      (node (ref "R334") (pin "1") (pinfunction "1_1") (pintype "passive"))
      (node (ref "R335") (pin "1") (pinfunction "1_1") (pintype "passive"))
      (node (ref "R501") (pin "1") (pinfunction "1_1") (pintype "passive"))
      (node (ref "R502") (pin "2") (pinfunction "2_2") (pintype "passive"))
      (node (ref "R90") (pin "1") (pinfunction "1_1") (pintype "passive"))
      (node (ref "R91") (pin "1") (pinfunction "1_1") (pintype "passive"))
      (node (ref "TP29") (pin "X") (pinfunction "X_X") (pintype "passive"))
      (node (ref "U5") (pin "31") (pinfunction "VDDIO_31") (pintype "passive"))
    )
    (net (code "46") (name "GND") (class "Default")
      (node (ref "C302") (pin "1") (pinfunction "1_1") (pintype "passive"))
      (node (ref "C303") (pin "2") (pinfunction "2_2") (pintype "passive"))
      (node (ref "C304") (pin "1") (pinfunction "1_1") (pintype "passive"))
      (node (ref "C308") (pin "1") (pinfunction "1_1") (pintype "passive"))
      (node (ref "C351") (pin "2") (pinfunction "2_2") (pintype "passive"))
      (node (ref "C352") (pin "2") (pinfunction "2_2") (pintype "passive"))
      (node (ref "C353") (pin "2") (pinfunction "2_2") (pintype "passive"))
      (node (ref "C354") (pin "2") (pinfunction "2_2") (pintype "passive"))
      (node (ref "C355") (pin "1") (pinfunction "1_1") (pintype "passive"))
      (node (ref "C356") (pin "2") (pinfunction "2_2") (pintype "passive"))
      (node (ref "C357") (pin "2") (pinfunction "2_2") (pintype "passive"))
      (node (ref "C359") (pin "1") (pinfunction "1_1") (pintype "passive"))
      (node (ref "C360") (pin "1") (pinfunction "1_1") (pintype "passive"))
      (node (ref "C40") (pin "1") (pinfunction "1_1") (pintype "passive"))
      (node (ref "C41") (pin "1") (pinfunction "1_1") (pintype "passive"))
      (node (ref "C42") (pin "1") (pinfunction "1_1") (pintype "passive"))
      (node (ref "C43") (pin "1") (pinfunction "1_1") (pintype "passive"))
      (node (ref "C44") (pin "2") (pinfunction "2_2") (pintype "passive"))
      (node (ref "C45") (pin "1") (pinfunction "1_1") (pintype "passive"))
      (node (ref "C46") (pin "1") (pinfunction "1_1") (pintype "passive"))
      (node (ref "C47") (pin "1") (pinfunction "1_1") (pintype "passive"))
      (node (ref "C48") (pin "1") (pinfunction "1_1") (pintype "passive"))
      (node (ref "C49") (pin "1") (pinfunction "1_1") (pintype "passive"))
      (node (ref "C84") (pin "1") (pinfunction "1_1") (pintype "passive"))
      (node (ref "DL2") (pin "C") (pinfunction "C_C") (pintype "passive"))
      (node (ref "R172") (pin "1") (pinfunction "1_1") (pintype "passive"))
      (node (ref "R173") (pin "2") (pinfunction "2_2") (pintype "passive"))
      (node (ref "R247") (pin "2") (pinfunction "2_2") (pintype "passive"))
      (node (ref "R324") (pin "1") (pinfunction "1_1") (pintype "passive"))
      (node (ref "R325") (pin "2") (pinfunction "2_2") (pintype "passive"))
      (node (ref "R460") (pin "1") (pinfunction "1_1") (pintype "passive"))
      (node (ref "R499") (pin "1") (pinfunction "1_1") (pintype "passive"))
      (node (ref "R500") (pin "1") (pinfunction "1_1") (pintype "passive"))
      (node (ref "R88") (pin "1") (pinfunction "1_1") (pintype "passive"))
      (node (ref "R89") (pin "1") (pinfunction "1_1") (pintype "passive"))
      (node (ref "R92") (pin "2") (pinfunction "2_2") (pintype "passive"))
      (node (ref "TP36") (pin "X") (pinfunction "X_X") (pintype "passive"))
      (node (ref "U26") (pin "13") (pinfunction "PGND_13") (pintype "passive"))
      (node (ref "U26") (pin "8") (pinfunction "AGND_8") (pintype "passive"))
      (node (ref "U30") (pin "3") (pinfunction "GND_3") (pintype "passive"))
      (node (ref "U30") (pin "7") (pinfunction "GND_PAD_7") (pintype "passive"))
      (node (ref "U5") (pin "13") (pinfunction "GND_13") (pintype "passive"))
      (node (ref "U5") (pin "53") (pinfunction "EPAD_53") (pintype "passive"))
    )
    (net (code "47") (name "Net-(C84-Pad2)") (class "Default")
      (node (ref "C84") (pin "2") (pinfunction "2_2") (pintype "passive"))
      (node (ref "R276") (pin "1") (pinfunction "1_1") (pintype "passive"))
      (node (ref "U5") (pin "46") (pinfunction "5_V_46") (pintype "passive"))
      (node (ref "U5") (pin "47") (pinfunction "5_V_47") (pintype "passive"))
      (node (ref "U5") (pin "48") (pinfunction "5_V_48") (pintype "passive"))
      (node (ref "U5") (pin "49") (pinfunction "5_V_49") (pintype "passive"))
    )
    (net (code "48") (name "Net-(C302-Pad2)") (class "Default")
      (node (ref "C302") (pin "2") (pinfunction "2_2") (pintype "passive"))
      (node (ref "C303") (pin "1") (pinfunction "1_1") (pintype "passive"))
      (node (ref "R504") (pin "1") (pinfunction "1_1") (pintype "passive"))
      (node (ref "U30") (pin "1") (pinfunction "IN_1") (pintype "passive"))
      (node (ref "U30") (pin "2") (pinfunction "IN_2") (pintype "passive"))
    )
    (net (code "49") (name "Net-(C350-Pad2)") (class "Default")
      (node (ref "C350") (pin "2") (pinfunction "2_2") (pintype "passive"))
      (node (ref "L10") (pin "1") (pinfunction "1_1") (pintype "passive"))
      (node (ref "U26") (pin "1") (pinfunction "SW_1") (pintype "passive"))
      (node (ref "U26") (pin "2") (pinfunction "SW_2") (pintype "passive"))
      (node (ref "U26") (pin "3") (pinfunction "SW_3") (pintype "passive"))
    )
    (net (code "50") (name "Net-(C351-Pad1)") (class "Default")
      (node (ref "C351") (pin "1") (pinfunction "1_1") (pintype "passive"))
      (node (ref "C352") (pin "1") (pinfunction "1_1") (pintype "passive"))
      (node (ref "C356") (pin "1") (pinfunction "1_1") (pintype "passive"))
      (node (ref "C357") (pin "1") (pinfunction "1_1") (pintype "passive"))
      (node (ref "R398") (pin "2") (pinfunction "2_2") (pintype "passive"))
      (node (ref "R505") (pin "1") (pinfunction "1_1") (pintype "passive"))
      (node (ref "U26") (pin "10") (pinfunction "VIN_10") (pintype "passive"))
      (node (ref "U26") (pin "11") (pinfunction "VIN_11") (pintype "passive"))
      (node (ref "U26") (pin "12") (pinfunction "VIN_12") (pintype "passive"))
    )
    (net (code "51") (name "Net-(C354-Pad1)") (class "Default")
      (node (ref "C354") (pin "1") (pinfunction "1_1") (pintype "passive"))
      (node (ref "C355") (pin "2") (pinfunction "2_2") (pintype "passive"))
      (node (ref "C359") (pin "2") (pinfunction "2_2") (pintype "passive"))
      (node (ref "L10") (pin "2") (pinfunction "2_2") (pintype "passive"))
      (node (ref "R498") (pin "2") (pinfunction "2_2") (pintype "passive"))
      (node (ref "R502") (pin "1") (pinfunction "1_1") (pintype "passive"))
      (node (ref "R503") (pin "2") (pinfunction "2_2") (pintype "passive"))
    )
    (net (code "52") (name "Net-(C358-Pad1)") (class "Default")
      (node (ref "C358") (pin "1") (pinfunction "1_1") (pintype "passive"))
      (node (ref "R503") (pin "1") (pinfunction "1_1") (pintype "passive"))
    )
    (net (code "53") (name "Net-(D4-PadC)") (class "Default")
      (node (ref "D4") (pin "C") (pinfunction "C_C") (pintype "passive"))
      (node (ref "D9") (pin "C") (pinfunction "C_C") (pintype "passive"))
      (node (ref "R504") (pin "2") (pinfunction "2_2") (pintype "passive"))
      (node (ref "R505") (pin "2") (pinfunction "2_2") (pintype "passive"))
    )
    (net (code "54") (name "Net-(DL2-PadA)") (class "Default")
      (node (ref "DL2") (pin "A") (pinfunction "A_A") (pintype "passive"))
      (node (ref "R106") (pin "1") (pinfunction "1_1") (pintype "passive"))
    )
    (net (code "55") (name "Net-(R234-Pad1)") (class "Default")
      (node (ref "R234") (pin "1") (pinfunction "1_1") (pintype "passive"))
      (node (ref "R236") (pin "2") (pinfunction "2_2") (pintype "passive"))
    )
    (net (code "56") (name "Net-(R235-Pad1)") (class "Default")
      (node (ref "R235") (pin "1") (pinfunction "1_1") (pintype "passive"))
      (node (ref "R331") (pin "2") (pinfunction "2_2") (pintype "passive"))
    )
    (net (code "57") (name "Net-(R236-Pad1)") (class "Default")
      (node (ref "R236") (pin "1") (pinfunction "1_1") (pintype "passive"))
      (node (ref "R244") (pin "2") (pinfunction "2_2") (pintype "passive"))
    )
    (net (code "58") (name "Net-(R237-Pad1)") (class "Default")
      (node (ref "R237") (pin "1") (pinfunction "1_1") (pintype "passive"))
      (node (ref "R332") (pin "2") (pinfunction "2_2") (pintype "passive"))
    )
    (net (code "59") (name "Net-(R244-Pad1)") (class "Default")
      (node (ref "R244") (pin "1") (pinfunction "1_1") (pintype "passive"))
      (node (ref "R246") (pin "1") (pinfunction "1_1") (pintype "passive"))
    )
    (net (code "60") (name "Net-(U5-GPIO0{slash}RTM_RST{slash}P0.0)") (class "Default")
      (node (ref "R369") (pin "2") (pinfunction "2_2") (pintype "passive"))
      (node (ref "U5") (pin "14") (pinfunction "GPIO0/RTM_RST/P0.0_14") (pintype "passive"))
    )
    (net (code "61") (name "Net-(U5-GPIO1{slash}P0.1)") (class "Default")
      (node (ref "R271") (pin "1") (pinfunction "1_1") (pintype "passive"))
      (node (ref "R367") (pin "2") (pinfunction "2_2") (pintype "passive"))
      (node (ref "U5") (pin "15") (pinfunction "GPIO1/P0.1_15") (pintype "passive"))
    )
    (net (code "62") (name "Net-(U5-GPIO2{slash}RTM_EN{slash}P0.2)") (class "Default")
      (node (ref "R370") (pin "2") (pinfunction "2_2") (pintype "passive"))
      (node (ref "U5") (pin "16") (pinfunction "GPIO2/RTM_EN/P0.2_16") (pintype "passive"))
    )
    (net (code "63") (name "Net-(U5-GPIO3{slash}P0.3)") (class "Default")
      (node (ref "R368") (pin "2") (pinfunction "2_2") (pintype "passive"))
      (node (ref "U5") (pin "17") (pinfunction "GPIO3/P0.3_17") (pintype "passive"))
    )
    (net (code "64") (name "Net-(U5-GPIO9{slash}P4.1)") (class "Default")
      (node (ref "R106") (pin "2") (pinfunction "2_2") (pintype "passive"))
      (node (ref "U5") (pin "51") (pinfunction "GPIO9/P4.1_51") (pintype "passive"))
    )
    (net (code "65") (name "Net-(U5-I2C1_IRQ{slash}P0.4)") (class "Default")
      (node (ref "R99") (pin "2") (pinfunction "2_2") (pintype "passive"))
      (node (ref "U5") (pin "18") (pinfunction "I2C1_IRQ/P0.4_18") (pintype "passive"))
    )
    (net (code "66") (name "Net-(U5-I2C1_SCL{slash}P1.0)") (class "Default")
      (node (ref "R100") (pin "2") (pinfunction "2_2") (pintype "passive"))
      (node (ref "U5") (pin "19") (pinfunction "I2C1_SCL/P1.0_19") (pintype "passive"))
    )
    (net (code "67") (name "Net-(U5-I2C1_SDA{slash}P1.1)") (class "Default")
      (node (ref "R101") (pin "2") (pinfunction "2_2") (pintype "passive"))
      (node (ref "U5") (pin "20") (pinfunction "I2C1_SDA/P1.1_20") (pintype "passive"))
    )
    (net (code "68") (name "Net-(U5-I2C2_IRQ{slash}P2.0)") (class "Default")
      (node (ref "R86") (pin "2") (pinfunction "2_2") (pintype "passive"))
      (node (ref "U5") (pin "21") (pinfunction "I2C2_IRQ/P2.0_21") (pintype "passive"))
    )
    (net (code "69") (name "Net-(U5-I2C2_SCL{slash}P2.1)") (class "Default")
      (node (ref "R87") (pin "2") (pinfunction "2_2") (pintype "passive"))
      (node (ref "U5") (pin "22") (pinfunction "I2C2_SCL/P2.1_22") (pintype "passive"))
    )
    (net (code "70") (name "Net-(U5-I2C2_SDA{slash}P2.2)") (class "Default")
      (node (ref "R104") (pin "2") (pinfunction "2_2") (pintype "passive"))
      (node (ref "U5") (pin "23") (pinfunction "I2C2_SDA/P2.2_23") (pintype "passive"))
    )
    (net (code "71") (name "Net-(U5-I2C3_SCL{slash}P2.3)") (class "Default")
      (node (ref "R102") (pin "2") (pinfunction "2_2") (pintype "passive"))
      (node (ref "U5") (pin "25") (pinfunction "I2C3_SCL/P2.3_25") (pintype "passive"))
    )
    (net (code "72") (name "Net-(U5-I2C3_SDA{slash}P2.4)") (class "Default")
      (node (ref "R103") (pin "2") (pinfunction "2_2") (pintype "passive"))
      (node (ref "U5") (pin "26") (pinfunction "I2C3_SDA/P2.4_26") (pintype "passive"))
    )
    (net (code "73") (name "Net-(U5-I2CADDR{slash}P3.3)") (class "Default")
      (node (ref "R91") (pin "2") (pinfunction "2_2") (pintype "passive"))
      (node (ref "R92") (pin "1") (pinfunction "1_1") (pintype "passive"))
      (node (ref "U5") (pin "52") (pinfunction "I2CADDR/P3.3_52") (pintype "passive"))
    )
    (net (code "74") (name "Net-(U5-LDO1_(VCCD))") (class "Default")
      (node (ref "C42") (pin "2") (pinfunction "2_2") (pintype "passive"))
      (node (ref "C43") (pin "2") (pinfunction "2_2") (pintype "passive"))
      (node (ref "U5") (pin "29") (pinfunction "LDO1_(VCCD)_29") (pintype "passive"))
    )
    (net (code "75") (name "Net-(U5-LDO2_(VDDD))") (class "Default")
      (node (ref "C44") (pin "1") (pinfunction "1_1") (pintype "passive"))
      (node (ref "C45") (pin "2") (pinfunction "2_2") (pintype "passive"))
      (node (ref "U5") (pin "30") (pinfunction "LDO2_(VDDD)_30") (pintype "passive"))
    )
    (net (code "76") (name "Net-(U5-PA_DBG_SCL)") (class "Default")
      (node (ref "R114") (pin "2") (pinfunction "2_2") (pintype "passive"))
      (node (ref "U5") (pin "12") (pinfunction "PA_DBG_SCL_12") (pintype "passive"))
    )
    (net (code "77") (name "Net-(U5-PA_DBG_SDA)") (class "Default")
      (node (ref "R113") (pin "2") (pinfunction "2_2") (pintype "passive"))
      (node (ref "U5") (pin "11") (pinfunction "PA_DBG_SDA_11") (pintype "passive"))
    )
    (net (code "78") (name "Net-(U5-VIN_3V3_(VSYS))") (class "Default")
      (node (ref "C47") (pin "2") (pinfunction "2_2") (pintype "passive"))
      (node (ref "C48") (pin "2") (pinfunction "2_2") (pintype "passive"))
      (node (ref "R274") (pin "1") (pinfunction "1_1") (pintype "passive"))
      (node (ref "R275") (pin "2") (pinfunction "2_2") (pintype "passive"))
      (node (ref "U5") (pin "32") (pinfunction "VIN_3V3_(VSYS)_32") (pintype "passive"))
    )
    (net (code "79") (name "Net-(U26-BOOT)") (class "Default")
      (node (ref "C350") (pin "1") (pinfunction "1_1") (pintype "passive"))
      (node (ref "U26") (pin "4") (pinfunction "BOOT_4") (pintype "passive"))
    )
    (net (code "80") (name "Net-(U26-EN)") (class "Default")
      (node (ref "C353") (pin "1") (pinfunction "1_1") (pintype "passive"))
      (node (ref "R398") (pin "1") (pinfunction "1_1") (pintype "passive"))
      (node (ref "R460") (pin "2") (pinfunction "2_2") (pintype "passive"))
      (node (ref "U26") (pin "9") (pinfunction "EN_9") (pintype "passive"))
    )
    (net (code "81") (name "Net-(U26-FB)") (class "Default")
      (node (ref "C358") (pin "2") (pinfunction "2_2") (pintype "passive"))
      (node (ref "R498") (pin "1") (pinfunction "1_1") (pintype "passive"))
      (node (ref "R500") (pin "2") (pinfunction "2_2") (pintype "passive"))
      (node (ref "U26") (pin "7") (pinfunction "FB_7") (pintype "passive"))
    )
    (net (code "82") (name "Net-(U26-RT)") (class "Default")
      (node (ref "R499") (pin "2") (pinfunction "2_2") (pintype "passive"))
      (node (ref "U26") (pin "6") (pinfunction "RT_6") (pintype "passive"))
    )
    (net (code "83") (name "Net-(U30-FB)") (class "Default")
      (node (ref "R246") (pin "2") (pinfunction "2_2") (pintype "passive"))
      (node (ref "R247") (pin "1") (pinfunction "1_1") (pintype "passive"))
      (node (ref "U30") (pin "4") (pinfunction "FB_4") (pintype "passive"))
    )
    (net (code "84") (name "Net-(U30-OUT)") (class "Default")
      (node (ref "C304") (pin "2") (pinfunction "2_2") (pintype "passive"))
      (node (ref "C308") (pin "2") (pinfunction "2_2") (pintype "passive"))
      (node (ref "R234") (pin "2") (pinfunction "2_2") (pintype "passive"))
      (node (ref "R501") (pin "2") (pinfunction "2_2") (pintype "passive"))
      (node (ref "U30") (pin "6") (pinfunction "OUT_6") (pintype "passive"))
    )
    (net (code "85") (name "SOM_VREG_MDPX3_1P8") (class "Default")
      (node (ref "R330") (pin "1") (pinfunction "1_1") (pintype "passive"))
      (node (ref "R331") (pin "1") (pinfunction "1_1") (pintype "passive"))
      (node (ref "R332") (pin "1") (pinfunction "1_1") (pintype "passive"))
    )
    (net (code "86") (name "unconnected-(R87-Pad1)") (class "Default")
      (node (ref "R87") (pin "1") (pinfunction "1_1") (pintype "passive"))
    )
    (net (code "87") (name "unconnected-(R102-Pad1)") (class "Default")
      (node (ref "R102") (pin "1") (pinfunction "1_1") (pintype "passive"))
    )
    (net (code "88") (name "unconnected-(R103-Pad1)") (class "Default")
      (node (ref "R103") (pin "1") (pinfunction "1_1") (pintype "passive"))
    )
    (net (code "89") (name "unconnected-(R104-Pad1)") (class "Default")
      (node (ref "R104") (pin "1") (pinfunction "1_1") (pintype "passive"))
    )
    (net (code "90") (name "unconnected-(R113-Pad1)") (class "Default")
      (node (ref "R113") (pin "1") (pinfunction "1_1") (pintype "passive"))
    )
    (net (code "91") (name "unconnected-(R114-Pad1)") (class "Default")
      (node (ref "R114") (pin "1") (pinfunction "1_1") (pintype "passive"))
    )
    (net (code "92") (name "unconnected-(U5-GPIO6{slash}FAULT#{slash}P3.0-Pad44)") (class "Default")
      (node (ref "U5") (pin "44") (pinfunction "GPIO6/FAULT#/P3.0_44") (pintype "passive+no_connect"))
    )
    (net (code "93") (name "unconnected-(U5-NC-Pad1)") (class "Default")
      (node (ref "U5") (pin "1") (pinfunction "NC_1") (pintype "passive+no_connect"))
    )
    (net (code "94") (name "unconnected-(U5-NC-Pad2)") (class "Default")
      (node (ref "U5") (pin "2") (pinfunction "NC_2") (pintype "passive+no_connect"))
    )
    (net (code "95") (name "unconnected-(U5-NC-Pad3)") (class "Default")
      (node (ref "U5") (pin "3") (pinfunction "NC_3") (pintype "passive+no_connect"))
    )
    (net (code "96") (name "unconnected-(U5-NC-Pad4)") (class "Default")
      (node (ref "U5") (pin "4") (pinfunction "NC_4") (pintype "passive+no_connect"))
    )
    (net (code "97") (name "unconnected-(U5-NC-Pad5)") (class "Default")
      (node (ref "U5") (pin "5") (pinfunction "NC_5") (pintype "passive+no_connect"))
    )
    (net (code "98") (name "unconnected-(U5-NC-Pad6)") (class "Default")
      (node (ref "U5") (pin "6") (pinfunction "NC_6") (pintype "passive+no_connect"))
    )
    (net (code "99") (name "unconnected-(U5-NC-Pad7)") (class "Default")
      (node (ref "U5") (pin "7") (pinfunction "NC_7") (pintype "passive+no_connect"))
    )
    (net (code "100") (name "unconnected-(U5-NC-Pad8)") (class "Default")
      (node (ref "U5") (pin "8") (pinfunction "NC_8") (pintype "passive+no_connect"))
    )
    (net (code "101") (name "unconnected-(U5-NC-Pad9)") (class "Default")
      (node (ref "U5") (pin "9") (pinfunction "NC_9") (pintype "passive+no_connect"))
    )
    (net (code "102") (name "unconnected-(U5-NC-Pad10)") (class "Default")
      (node (ref "U5") (pin "10") (pinfunction "NC_10") (pintype "passive+no_connect"))
    )
    (net (code "103") (name "unconnected-(U26-PG-Pad5)") (class "Default")
      (node (ref "U26") (pin "5") (pinfunction "PG_5") (pintype "passive+no_connect"))
    )
    (net (code "104") (name "unconnected-(U30-NC-Pad5)") (class "Default")
      (node (ref "U30") (pin "5") (pinfunction "NC_5") (pintype "passive+no_connect"))
    )
  )
)
